# untitled.net
KiCad netlist of a schematic drawn in EAGLE
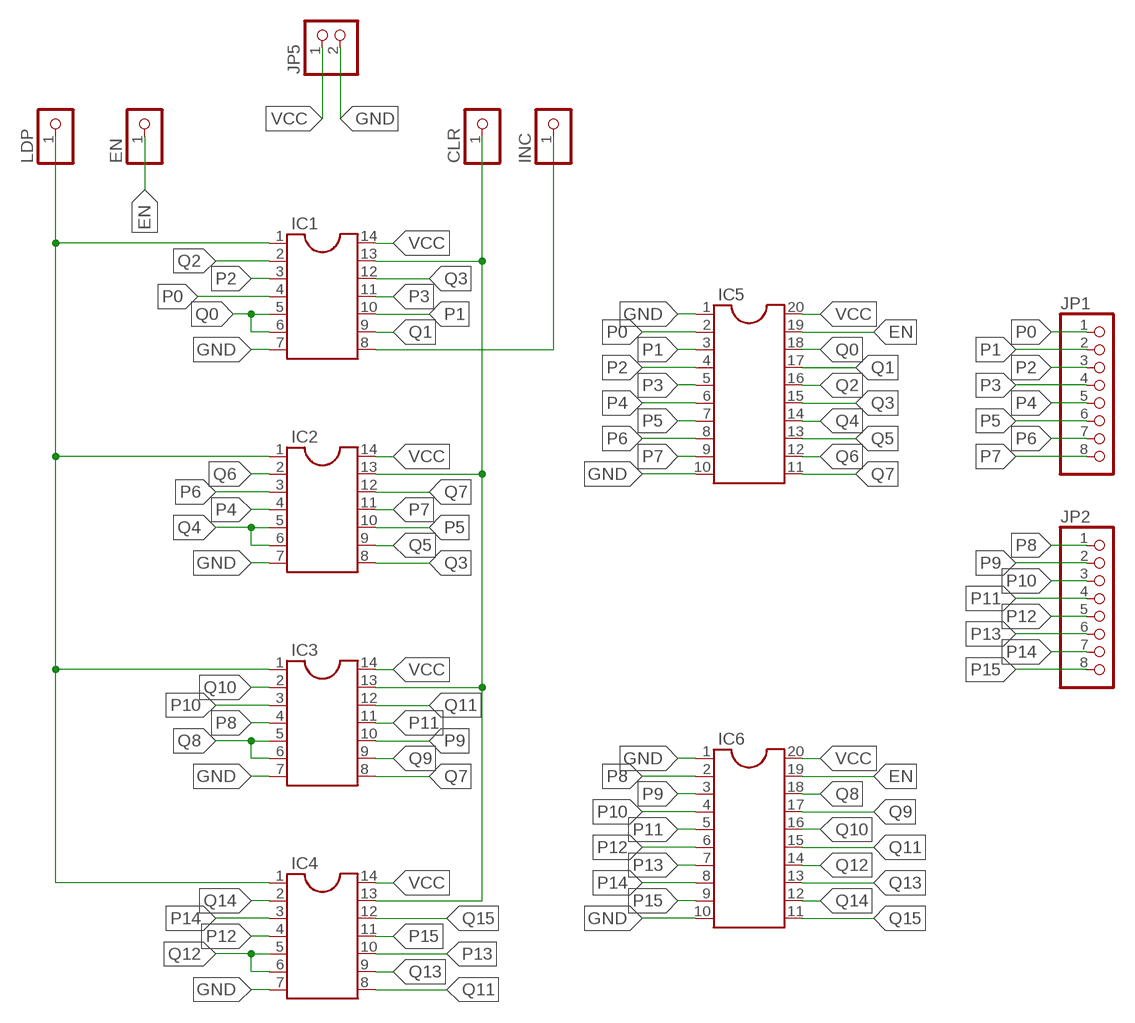
[diagram p0: schematic, sheet 1]

(export (version "E")
  (design (tool "Eeschema 10.0.6"))
  (components
    (comp (ref "CLR")
      (value "PINHD-1X1")
      (footprint "eagle-import:1X01")
      (libsource (lib "eagle-import") (part "PINHD-1X1"))
    )
    (comp (ref "EN")
      (value "PINHD-1X1")
      (footprint "eagle-import:1X01")
      (libsource (lib "eagle-import") (part "PINHD-1X1"))
    )
    (comp (ref "IC1")
      (value "DIL14")
      (footprint "eagle-import:DIL14")
      (libsource (lib "eagle-import") (part "DIL14"))
    )
    (comp (ref "IC2")
      (value "DIL14")
      (footprint "eagle-import:DIL14")
      (libsource (lib "eagle-import") (part "DIL14"))
    )
    (comp (ref "IC3")
      (value "DIL14")
      (footprint "eagle-import:DIL14")
      (libsource (lib "eagle-import") (part "DIL14"))
    )
    (comp (ref "IC4")
      (value "DIL14")
      (footprint "eagle-import:DIL14")
      (libsource (lib "eagle-import") (part "DIL14"))
    )
    (comp (ref "IC5")
      (value "DIL20")
      (footprint "eagle-import:DIL20")
      (libsource (lib "eagle-import") (part "DIL20"))
    )
    (comp (ref "IC6")
      (value "DIL20")
      (footprint "eagle-import:DIL20")
      (libsource (lib "eagle-import") (part "DIL20"))
    )
    (comp (ref "INC")
      (value "PINHD-1X1")
      (footprint "eagle-import:1X01")
      (libsource (lib "eagle-import") (part "PINHD-1X1"))
    )
    (comp (ref "JP1")
      (value "PINHD-1X8")
      (footprint "eagle-import:1X08")
      (libsource (lib "eagle-import") (part "PINHD-1X8"))
    )
    (comp (ref "JP2")
      (value "PINHD-1X8")
      (footprint "eagle-import:1X08")
      (libsource (lib "eagle-import") (part "PINHD-1X8"))
    )
    (comp (ref "JP5")
      (value "PINHD-1X2")
      (footprint "eagle-import:1X02")
      (libsource (lib "eagle-import") (part "PINHD-1X2"))
    )
    (comp (ref "LDP")
      (value "PINHD-1X1")
      (footprint "eagle-import:1X01")
      (libsource (lib "eagle-import") (part "PINHD-1X1"))
    )
  )
  (nets
    (net (code "1") (name "EN") (class "Default")
      (node (ref "EN") (pin "1") (pinfunction "1_1") (pintype "passive"))
      (node (ref "IC5") (pin "19") (pinfunction "19_19") (pintype "passive"))
      (node (ref "IC6") (pin "19") (pinfunction "19_19") (pintype "passive"))
    )
    (net (code "2") (name "GND") (class "Default")
      (node (ref "IC1") (pin "7") (pinfunction "7_7") (pintype "passive"))
      (node (ref "IC2") (pin "7") (pinfunction "7_7") (pintype "passive"))
      (node (ref "IC3") (pin "7") (pinfunction "7_7") (pintype "passive"))
      (node (ref "IC4") (pin "7") (pinfunction "7_7") (pintype "passive"))
      (node (ref "IC5") (pin "1") (pinfunction "1_1") (pintype "passive"))
      (node (ref "IC5") (pin "10") (pinfunction "10_10") (pintype "passive"))
      (node (ref "IC6") (pin "1") (pinfunction "1_1") (pintype "passive"))
      (node (ref "IC6") (pin "10") (pinfunction "10_10") (pintype "passive"))
      (node (ref "JP5") (pin "2") (pinfunction "2_2") (pintype "passive"))
    )
    (net (code "3") (name "Net-(CLR-Pad1)") (class "Default")
      (node (ref "CLR") (pin "1") (pinfunction "1_1") (pintype "passive"))
      (node (ref "IC1") (pin "13") (pinfunction "13_13") (pintype "passive"))
      (node (ref "IC2") (pin "13") (pinfunction "13_13") (pintype "passive"))
      (node (ref "IC3") (pin "13") (pinfunction "13_13") (pintype "passive"))
      (node (ref "IC4") (pin "13") (pinfunction "13_13") (pintype "passive"))
    )
    (net (code "4") (name "Net-(IC1-Pad1)") (class "Default")
      (node (ref "IC1") (pin "1") (pinfunction "1_1") (pintype "passive"))
      (node (ref "IC2") (pin "1") (pinfunction "1_1") (pintype "passive"))
      (node (ref "IC3") (pin "1") (pinfunction "1_1") (pintype "passive"))
      (node (ref "IC4") (pin "1") (pinfunction "1_1") (pintype "passive"))
      (node (ref "LDP") (pin "1") (pinfunction "1_1") (pintype "passive"))
    )
    (net (code "5") (name "Net-(IC1-Pad8)") (class "Default")
      (node (ref "IC1") (pin "8") (pinfunction "8_8") (pintype "passive"))
      (node (ref "INC") (pin "1") (pinfunction "1_1") (pintype "passive"))
    )
    (net (code "6") (name "P0") (class "Default")
      (node (ref "IC1") (pin "4") (pinfunction "4_4") (pintype "passive"))
      (node (ref "IC5") (pin "2") (pinfunction "2_2") (pintype "passive"))
      (node (ref "JP1") (pin "1") (pinfunction "1_1") (pintype "passive"))
    )
    (net (code "7") (name "P1") (class "Default")
      (node (ref "IC1") (pin "10") (pinfunction "10_10") (pintype "passive"))
      (node (ref "IC5") (pin "3") (pinfunction "3_3") (pintype "passive"))
      (node (ref "JP1") (pin "2") (pinfunction "2_2") (pintype "passive"))
    )
    (net (code "8") (name "P2") (class "Default")
      (node (ref "IC1") (pin "3") (pinfunction "3_3") (pintype "passive"))
      (node (ref "IC5") (pin "4") (pinfunction "4_4") (pintype "passive"))
      (node (ref "JP1") (pin "3") (pinfunction "3_3") (pintype "passive"))
    )
    (net (code "9") (name "P3") (class "Default")
      (node (ref "IC1") (pin "11") (pinfunction "11_11") (pintype "passive"))
      (node (ref "IC5") (pin "5") (pinfunction "5_5") (pintype "passive"))
      (node (ref "JP1") (pin "4") (pinfunction "4_4") (pintype "passive"))
    )
    (net (code "10") (name "P4") (class "Default")
      (node (ref "IC2") (pin "4") (pinfunction "4_4") (pintype "passive"))
      (node (ref "IC5") (pin "6") (pinfunction "6_6") (pintype "passive"))
      (node (ref "JP1") (pin "5") (pinfunction "5_5") (pintype "passive"))
    )
    (net (code "11") (name "P5") (class "Default")
      (node (ref "IC2") (pin "10") (pinfunction "10_10") (pintype "passive"))
      (node (ref "IC5") (pin "7") (pinfunction "7_7") (pintype "passive"))
      (node (ref "JP1") (pin "6") (pinfunction "6_6") (pintype "passive"))
    )
    (net (code "12") (name "P6") (class "Default")
      (node (ref "IC2") (pin "3") (pinfunction "3_3") (pintype "passive"))
      (node (ref "IC5") (pin "8") (pinfunction "8_8") (pintype "passive"))
      (node (ref "JP1") (pin "7") (pinfunction "7_7") (pintype "passive"))
    )
    (net (code "13") (name "P7") (class "Default")
      (node (ref "IC2") (pin "11") (pinfunction "11_11") (pintype "passive"))
      (node (ref "IC5") (pin "9") (pinfunction "9_9") (pintype "passive"))
      (node (ref "JP1") (pin "8") (pinfunction "8_8") (pintype "passive"))
    )
    (net (code "14") (name "P8") (class "Default")
      (node (ref "IC3") (pin "4") (pinfunction "4_4") (pintype "passive"))
      (node (ref "IC6") (pin "2") (pinfunction "2_2") (pintype "passive"))
      (node (ref "JP2") (pin "1") (pinfunction "1_1") (pintype "passive"))
    )
    (net (code "15") (name "P9") (class "Default")
      (node (ref "IC3") (pin "10") (pinfunction "10_10") (pintype "passive"))
      (node (ref "IC6") (pin "3") (pinfunction "3_3") (pintype "passive"))
      (node (ref "JP2") (pin "2") (pinfunction "2_2") (pintype "passive"))
    )
    (net (code "16") (name "P10") (class "Default")
      (node (ref "IC3") (pin "3") (pinfunction "3_3") (pintype "passive"))
      (node (ref "IC6") (pin "4") (pinfunction "4_4") (pintype "passive"))
      (node (ref "JP2") (pin "3") (pinfunction "3_3") (pintype "passive"))
    )
    (net (code "17") (name "P11") (class "Default")
      (node (ref "IC3") (pin "11") (pinfunction "11_11") (pintype "passive"))
      (node (ref "IC6") (pin "5") (pinfunction "5_5") (pintype "passive"))
      (node (ref "JP2") (pin "4") (pinfunction "4_4") (pintype "passive"))
    )
    (net (code "18") (name "P12") (class "Default")
      (node (ref "IC4") (pin "4") (pinfunction "4_4") (pintype "passive"))
      (node (ref "IC6") (pin "6") (pinfunction "6_6") (pintype "passive"))
      (node (ref "JP2") (pin "5") (pinfunction "5_5") (pintype "passive"))
    )
    (net (code "19") (name "P13") (class "Default")
      (node (ref "IC4") (pin "10") (pinfunction "10_10") (pintype "passive"))
      (node (ref "IC6") (pin "7") (pinfunction "7_7") (pintype "passive"))
      (node (ref "JP2") (pin "6") (pinfunction "6_6") (pintype "passive"))
    )
    (net (code "20") (name "P14") (class "Default")
      (node (ref "IC4") (pin "3") (pinfunction "3_3") (pintype "passive"))
      (node (ref "IC6") (pin "8") (pinfunction "8_8") (pintype "passive"))
      (node (ref "JP2") (pin "7") (pinfunction "7_7") (pintype "passive"))
    )
    (net (code "21") (name "P15") (class "Default")
      (node (ref "IC4") (pin "11") (pinfunction "11_11") (pintype "passive"))
      (node (ref "IC6") (pin "9") (pinfunction "9_9") (pintype "passive"))
      (node (ref "JP2") (pin "8") (pinfunction "8_8") (pintype "passive"))
    )
    (net (code "22") (name "Q0") (class "Default")
      (node (ref "IC1") (pin "5") (pinfunction "5_5") (pintype "passive"))
      (node (ref "IC1") (pin "6") (pinfunction "6_6") (pintype "passive"))
      (node (ref "IC5") (pin "18") (pinfunction "18_18") (pintype "passive"))
    )
    (net (code "23") (name "Q1") (class "Default")
      (node (ref "IC1") (pin "9") (pinfunction "9_9") (pintype "passive"))
      (node (ref "IC5") (pin "17") (pinfunction "17_17") (pintype "passive"))
    )
    (net (code "24") (name "Q2") (class "Default")
      (node (ref "IC1") (pin "2") (pinfunction "2_2") (pintype "passive"))
      (node (ref "IC5") (pin "16") (pinfunction "16_16") (pintype "passive"))
    )
    (net (code "25") (name "Q3") (class "Default")
      (node (ref "IC1") (pin "12") (pinfunction "12_12") (pintype "passive"))
      (node (ref "IC2") (pin "8") (pinfunction "8_8") (pintype "passive"))
      (node (ref "IC5") (pin "15") (pinfunction "15_15") (pintype "passive"))
    )
    (net (code "26") (name "Q4") (class "Default")
      (node (ref "IC2") (pin "5") (pinfunction "5_5") (pintype "passive"))
      (node (ref "IC2") (pin "6") (pinfunction "6_6") (pintype "passive"))
      (node (ref "IC5") (pin "14") (pinfunction "14_14") (pintype "passive"))
    )
    (net (code "27") (name "Q5") (class "Default")
      (node (ref "IC2") (pin "9") (pinfunction "9_9") (pintype "passive"))
      (node (ref "IC5") (pin "13") (pinfunction "13_13") (pintype "passive"))
    )
    (net (code "28") (name "Q6") (class "Default")
      (node (ref "IC2") (pin "2") (pinfunction "2_2") (pintype "passive"))
      (node (ref "IC5") (pin "12") (pinfunction "12_12") (pintype "passive"))
    )
    (net (code "29") (name "Q7") (class "Default")
      (node (ref "IC2") (pin "12") (pinfunction "12_12") (pintype "passive"))
      (node (ref "IC3") (pin "8") (pinfunction "8_8") (pintype "passive"))
      (node (ref "IC5") (pin "11") (pinfunction "11_11") (pintype "passive"))
    )
    (net (code "30") (name "Q8") (class "Default")
      (node (ref "IC3") (pin "5") (pinfunction "5_5") (pintype "passive"))
      (node (ref "IC3") (pin "6") (pinfunction "6_6") (pintype "passive"))
      (node (ref "IC6") (pin "18") (pinfunction "18_18") (pintype "passive"))
    )
    (net (code "31") (name "Q9") (class "Default")
      (node (ref "IC3") (pin "9") (pinfunction "9_9") (pintype "passive"))
      (node (ref "IC6") (pin "17") (pinfunction "17_17") (pintype "passive"))
    )
    (net (code "32") (name "Q10") (class "Default")
      (node (ref "IC3") (pin "2") (pinfunction "2_2") (pintype "passive"))
      (node (ref "IC6") (pin "16") (pinfunction "16_16") (pintype "passive"))
    )
    (net (code "33") (name "Q11") (class "Default")
      (node (ref "IC3") (pin "12") (pinfunction "12_12") (pintype "passive"))
      (node (ref "IC4") (pin "8") (pinfunction "8_8") (pintype "passive"))
      (node (ref "IC6") (pin "15") (pinfunction "15_15") (pintype "passive"))
    )
    (net (code "34") (name "Q12") (class "Default")
      (node (ref "IC4") (pin "5") (pinfunction "5_5") (pintype "passive"))
      (node (ref "IC4") (pin "6") (pinfunction "6_6") (pintype "passive"))
      (node (ref "IC6") (pin "14") (pinfunction "14_14") (pintype "passive"))
    )
    (net (code "35") (name "Q13") (class "Default")
      (node (ref "IC4") (pin "9") (pinfunction "9_9") (pintype "passive"))
      (node (ref "IC6") (pin "13") (pinfunction "13_13") (pintype "passive"))
    )
    (net (code "36") (name "Q14") (class "Default")
      (node (ref "IC4") (pin "2") (pinfunction "2_2") (pintype "passive"))
      (node (ref "IC6") (pin "12") (pinfunction "12_12") (pintype "passive"))
    )
    (net (code "37") (name "Q15") (class "Default")
      (node (ref "IC4") (pin "12") (pinfunction "12_12") (pintype "passive"))
      (node (ref "IC6") (pin "11") (pinfunction "11_11") (pintype "passive"))
    )
    (net (code "38") (name "VCC") (class "Default")
      (node (ref "IC1") (pin "14") (pinfunction "14_14") (pintype "passive"))
      (node (ref "IC2") (pin "14") (pinfunction "14_14") (pintype "passive"))
      (node (ref "IC3") (pin "14") (pinfunction "14_14") (pintype "passive"))
      (node (ref "IC4") (pin "14") (pinfunction "14_14") (pintype "passive"))
      (node (ref "IC5") (pin "20") (pinfunction "20_20") (pintype "passive"))
      (node (ref "IC6") (pin "20") (pinfunction "20_20") (pintype "passive"))
      (node (ref "JP5") (pin "1") (pinfunction "1_1") (pintype "passive"))
    )
  )
)
